# project4_v1.net
KiCad netlist of a schematic drawn in Altium Designer
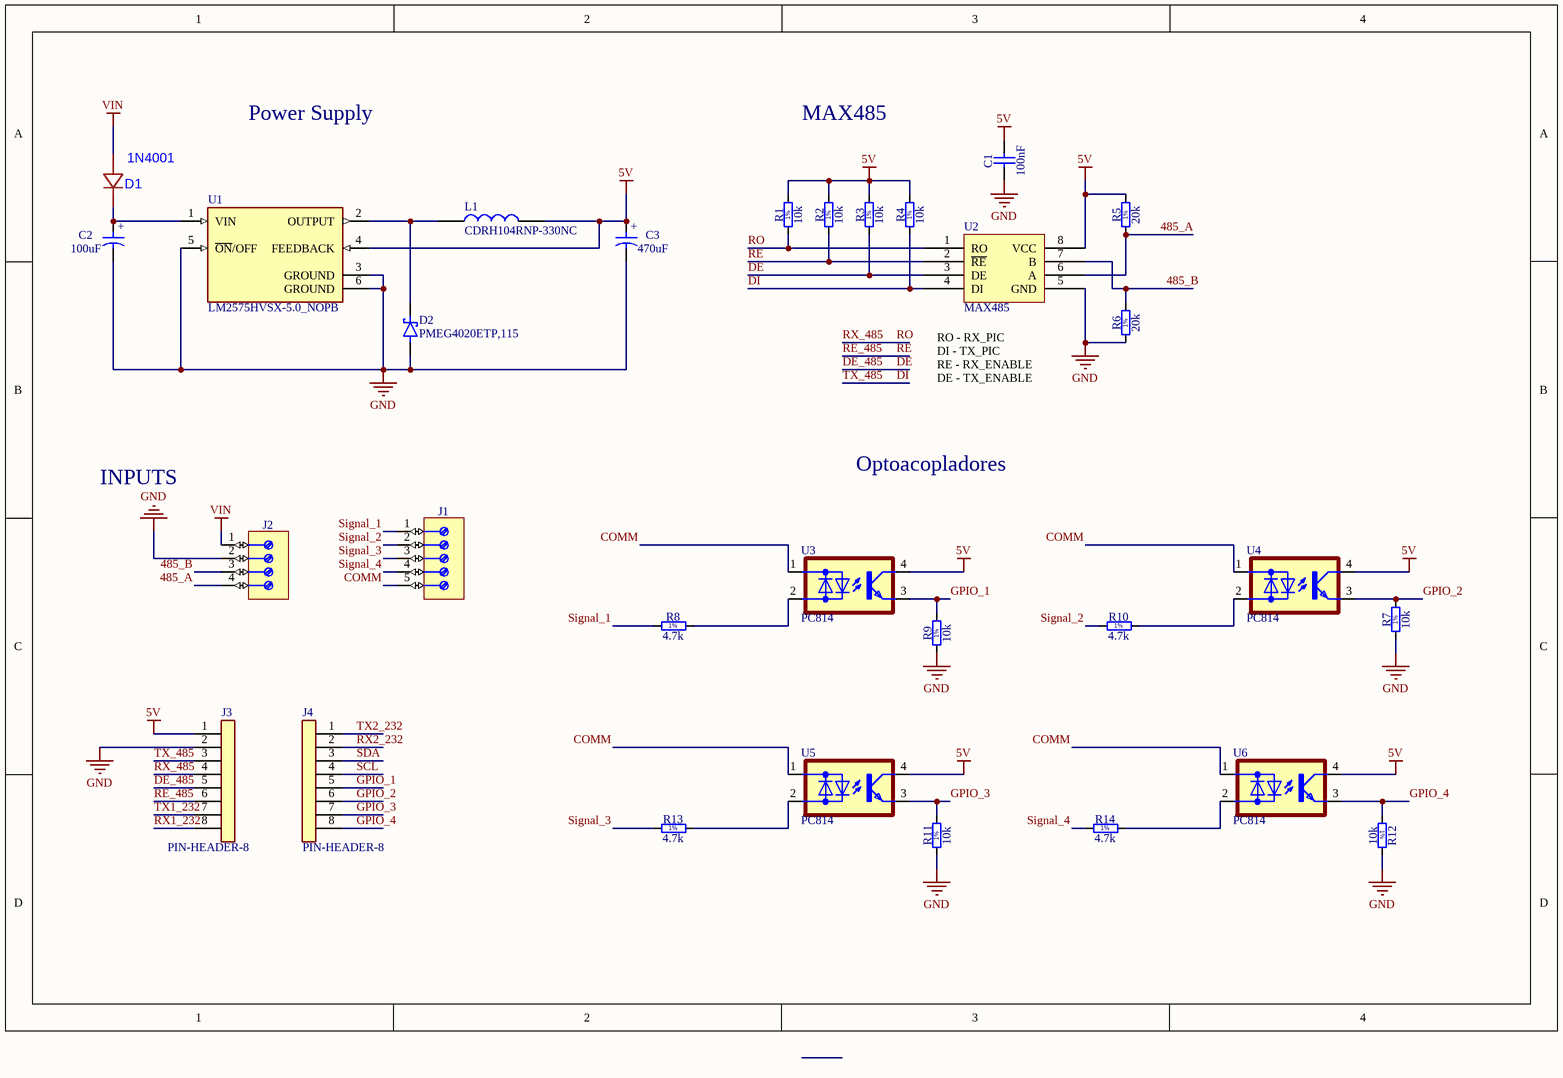
[diagram p0: project4_v1.SchDoc]

(export (version "E")
  (design (tool "Eeschema 10.0.6"))
  (components
    (comp (ref "C1")
      (value "100nF")
      (footprint "CAPC2012X135N")
      (description "Non-polarised capacitor")
      (fields
        (field (name "PART NUMBER") "CC0805_100NF_50V_10%_X7R")
        (field (name "VOLTAGE") "50V")
        (field (name "AUTHOR") "CERN DEM JLC")
      )
      (libsource (lib "Capacitors") (part "Capacitor - non polarized"))
    )
    (comp (ref "C2")
      (value "100uF")
      (footprint "CAPAE830X1020N")
      (description "Polarised capacitor")
      (fields
        (field (name "PART NUMBER") "CAE830-1020_100UF_35V_20%")
        (field (name "VOLTAGE") "35V")
        (field (name "AUTHOR") "CERN DEM JLC")
      )
      (libsource (lib "Capacitors") (part "Capacitor - polarized"))
    )
    (comp (ref "C3")
      (value "470uF")
      (footprint "CAPAE1030X1020N")
      (description "Polarised capacitor")
      (fields
        (field (name "PART NUMBER") "CAE1030-1020_470UF_25V_20%")
        (field (name "VOLTAGE") "25V")
        (field (name "AUTHOR") "CERN DEM JLC")
      )
      (libsource (lib "Capacitors") (part "Capacitor - polarized"))
    )
    (comp (ref "D1")
      (value "1N4001")
      (footprint "SMA_L4.5-W2.7-LS5.2-RD")
      (fields (field (name "MANUFACTURER") "JSMSEMI(杰盛微)") (field (name "MANUFACTURER PART") "1N4001 M1"))
      (libsource (lib "Galio-complete") (part "1N4001 M1"))
    )
    (comp (ref "D2")
      (value "PMEG4020ETP,115")
      (footprint "SODFL4725X110N")
      (description "Diode Schottky 40V 2A Surface Mount SOD-128/CFP5")
      (fields (field (name "MF") "Nexperia USA"))
      (libsource (lib "Galio-complete") (part "PMEG4020ETP,115"))
    )
    (comp (ref "J1")
      (value "TRT5")
      (footprint "TRT_5_3.81_PLUG")
      (description "TRT_5")
      (libsource (lib "Galio-connectors") (part "TRT_5"))
    )
    (comp (ref "J2")
      (value "TRT4")
      (footprint "TRT_4_3.81_PLUG")
      (description "TRT_4")
      (libsource (lib "Galio-connectors") (part "TRT_4"))
    )
    (comp (ref "J3")
      (value "PIN-HEADER-8")
      (footprint "PIN-HEADER-8-FEMALE")
      (fields (field (name "MP") "MTSW-108-07-G-S-208"))
      (libsource (lib "") (part "PIN-HEADER-8_1"))
    )
    (comp (ref "J4")
      (value "PIN-HEADER-8")
      (footprint "PIN-HEADER-8-FEMALE")
      (fields (field (name "MP") "MTSW-108-07-G-S-208"))
      (libsource (lib "Galio-connectors") (part "PIN-HEADER-8"))
    )
    (comp (ref "L1")
      (value "CDRH104RNP-330NC")
      (footprint "IND-SMD_L10.2-W10.0")
      (description "Power Inductors - SMD 33uH 2.2A,33 H Shielded Inductor 2.2 A 93mOhm Max Nonstandard")
      (fields (field (name "MOUSER PART NUMBER") "851-CDRH104RNP-330NC"))
      (libsource (lib "Galio-complete") (part "CDRH104RNP-330NC"))
    )
    (comp (ref "R1")
      (value "10k")
      (footprint "RESC2012X60N")
      (description "Resistor - 1%")
      (fields
        (field (name "PART NUMBER") "R0805_10K_1%_0.125W_100PPM")
        (field (name "POWER") "0.125W")
        (field (name "AUTHOR") "CERN DEM JLC")
      )
      (libsource (lib "Resistors") (part "Resistor - 1%"))
    )
    (comp (ref "R2")
      (value "10k")
      (footprint "RESC2012X60N")
      (description "Resistor - 1%")
      (fields
        (field (name "PART NUMBER") "R0805_10K_1%_0.125W_100PPM")
        (field (name "POWER") "0.125W")
        (field (name "AUTHOR") "CERN DEM JLC")
      )
      (libsource (lib "Resistors") (part "Resistor - 1%"))
    )
    (comp (ref "R3")
      (value "10k")
      (footprint "RESC2012X60N")
      (description "Resistor - 1%")
      (fields
        (field (name "PART NUMBER") "R0805_10K_1%_0.125W_100PPM")
        (field (name "POWER") "0.125W")
        (field (name "AUTHOR") "CERN DEM JLC")
      )
      (libsource (lib "Resistors") (part "Resistor - 1%"))
    )
    (comp (ref "R4")
      (value "10k")
      (footprint "RESC2012X60N")
      (description "Resistor - 1%")
      (fields
        (field (name "PART NUMBER") "R0805_10K_1%_0.125W_100PPM")
        (field (name "POWER") "0.125W")
        (field (name "AUTHOR") "CERN DEM JLC")
      )
      (libsource (lib "Resistors") (part "Resistor - 1%"))
    )
    (comp (ref "R5")
      (value "20k")
      (footprint "RESC2012X60N")
      (description "Resistor - 1%")
      (fields
        (field (name "PART NUMBER") "R0805_20K_1%_0.125W_100PPM")
        (field (name "POWER") "0.125W")
        (field (name "AUTHOR") "CERN DEM JLC")
      )
      (libsource (lib "Resistors") (part "Resistor - 1%"))
    )
    (comp (ref "R6")
      (value "20k")
      (footprint "RESC2012X60N")
      (description "Resistor - 1%")
      (fields
        (field (name "PART NUMBER") "R0805_20K_1%_0.125W_100PPM")
        (field (name "POWER") "0.125W")
        (field (name "AUTHOR") "CERN DEM JLC")
      )
      (libsource (lib "Resistors") (part "Resistor - 1%"))
    )
    (comp (ref "R7")
      (value "10k")
      (footprint "RESC2012X60N")
      (description "Resistor - 1%")
      (fields
        (field (name "PART NUMBER") "R0805_10K_1%_0.125W_100PPM")
        (field (name "POWER") "0.125W")
        (field (name "AUTHOR") "CERN DEM JLC")
      )
      (libsource (lib "Resistors") (part "Resistor - 1%"))
    )
    (comp (ref "R8")
      (value "4.7k")
      (footprint "RESC2012X60N")
      (description "Resistor - 1%")
      (fields
        (field (name "PART NUMBER") "R0805_10K_1%_0.125W_100PPM")
        (field (name "POWER") "0.125W")
        (field (name "AUTHOR") "CERN DEM JLC")
      )
      (libsource (lib "Resistors") (part "Resistor - 1%"))
    )
    (comp (ref "R9")
      (value "10k")
      (footprint "RESC2012X60N")
      (description "Resistor - 1%")
      (fields
        (field (name "PART NUMBER") "R0805_10K_1%_0.125W_100PPM")
        (field (name "POWER") "0.125W")
        (field (name "AUTHOR") "CERN DEM JLC")
      )
      (libsource (lib "Resistors") (part "Resistor - 1%"))
    )
    (comp (ref "R10")
      (value "4.7k")
      (footprint "RESC2012X60N")
      (description "Resistor - 1%")
      (fields
        (field (name "PART NUMBER") "R0805_10K_1%_0.125W_100PPM")
        (field (name "POWER") "0.125W")
        (field (name "AUTHOR") "CERN DEM JLC")
      )
      (libsource (lib "Resistors") (part "Resistor - 1%"))
    )
    (comp (ref "R11")
      (value "10k")
      (footprint "RESC2012X60N")
      (description "Resistor - 1%")
      (fields
        (field (name "PART NUMBER") "R0805_10K_1%_0.125W_100PPM")
        (field (name "POWER") "0.125W")
        (field (name "AUTHOR") "CERN DEM JLC")
      )
      (libsource (lib "Resistors") (part "Resistor - 1%"))
    )
    (comp (ref "R12")
      (value "10k")
      (footprint "RESC2012X60N")
      (description "Resistor - 1%")
      (fields
        (field (name "PART NUMBER") "R0805_10K_1%_0.125W_100PPM")
        (field (name "POWER") "0.125W")
        (field (name "AUTHOR") "CERN DEM JLC")
      )
      (libsource (lib "Resistors") (part "Resistor - 1%"))
    )
    (comp (ref "R13")
      (value "4.7k")
      (footprint "RESC2012X60N")
      (description "Resistor - 1%")
      (fields
        (field (name "PART NUMBER") "R0805_10K_1%_0.125W_100PPM")
        (field (name "POWER") "0.125W")
        (field (name "AUTHOR") "CERN DEM JLC")
      )
      (libsource (lib "Resistors") (part "Resistor - 1%"))
    )
    (comp (ref "R14")
      (value "4.7k")
      (footprint "RESC2012X60N")
      (description "Resistor - 1%")
      (fields
        (field (name "PART NUMBER") "R0805_10K_1%_0.125W_100PPM")
        (field (name "POWER") "0.125W")
        (field (name "AUTHOR") "CERN DEM JLC")
      )
      (libsource (lib "Resistors") (part "Resistor - 1%"))
    )
    (comp (ref "U1")
      (value "LM2575HVSX-5.0_NOPB")
      (footprint "TO-263-5_L10.0-W8.4-P1.70-LS15.3-BR")
      (fields (field (name "MF") "UMW") (field (name "MP") "LM2575S-5.0"))
      (libsource (lib "Galio-complete") (part "LM2575HVSX-5.0_NOPB"))
    )
    (comp (ref "U2")
      (value "MAX485")
      (footprint "SOIC8-N_MC")
      (libsource (lib "Galio-complete") (part "MAX485"))
    )
    (comp (ref "U3")
      (value "PC814")
      (footprint "PC814BS")
      (description "Optoacoplador com saÃ­da de transistor de 5000Vrms, 1 canal, 4 componentes SMD.")
      (fields (field (name "MF") "Essentra Components"))
      (libsource (lib "Galio-complete") (part "PC814"))
    )
    (comp (ref "U4")
      (value "PC814")
      (footprint "PC814BS")
      (description "Optoacoplador com saÃ­da de transistor de 5000Vrms, 1 canal, 4 componentes SMD.")
      (fields (field (name "MF") "Essentra Components"))
      (libsource (lib "Galio-complete") (part "PC814"))
    )
    (comp (ref "U5")
      (value "PC814")
      (footprint "PC814BS")
      (description "Optoacoplador com saÃ­da de transistor de 5000Vrms, 1 canal, 4 componentes SMD.")
      (fields (field (name "MF") "Essentra Components"))
      (libsource (lib "Galio-complete") (part "PC814"))
    )
    (comp (ref "U6")
      (value "PC814")
      (footprint "PC814BS")
      (description "Optoacoplador com saÃ­da de transistor de 5000Vrms, 1 canal, 4 componentes SMD.")
      (fields (field (name "MF") "Essentra Components"))
      (libsource (lib "Galio-complete") (part "PC814"))
    )
  )
  (nets
    (net (code "1") (name "/485_A") (class "Default")
      (node (ref "J2") (pin "4") (pinfunction "4_4") (pintype "bidirectional"))
      (node (ref "R5") (pin "1") (pinfunction "1_1") (pintype "passive"))
      (node (ref "U2") (pin "6") (pinfunction "A_6") (pintype "passive"))
    )
    (net (code "2") (name "/485_B") (class "Default")
      (node (ref "J2") (pin "3") (pinfunction "3_3") (pintype "bidirectional"))
      (node (ref "R6") (pin "2") (pinfunction "2_2") (pintype "passive"))
      (node (ref "U2") (pin "7") (pinfunction "B_7") (pintype "passive"))
    )
    (net (code "3") (name "/COMM") (class "Default")
      (node (ref "J1") (pin "5") (pinfunction "5_5") (pintype "bidirectional"))
      (node (ref "U3") (pin "1") (pinfunction "AC1_1") (pintype "passive"))
      (node (ref "U4") (pin "1") (pinfunction "AC1_1") (pintype "passive"))
      (node (ref "U5") (pin "1") (pinfunction "AC1_1") (pintype "passive"))
      (node (ref "U6") (pin "1") (pinfunction "AC1_1") (pintype "passive"))
    )
    (net (code "4") (name "/DE") (class "Default")
      (node (ref "J3") (pin "5") (pintype "passive"))
      (node (ref "R3") (pin "1") (pinfunction "1_1") (pintype "passive"))
      (node (ref "U2") (pin "3") (pinfunction "DE_3") (pintype "passive"))
    )
    (net (code "5") (name "/DI") (class "Default")
      (node (ref "J3") (pin "3") (pintype "passive"))
      (node (ref "R4") (pin "1") (pinfunction "1_1") (pintype "passive"))
      (node (ref "U2") (pin "4") (pinfunction "DI_4") (pintype "passive"))
    )
    (net (code "6") (name "/GPIO_1") (class "Default")
      (node (ref "J4") (pin "5") (pintype "passive"))
      (node (ref "R9") (pin "2") (pinfunction "2_2") (pintype "passive"))
      (node (ref "U3") (pin "3") (pinfunction "E_3") (pintype "passive"))
    )
    (net (code "7") (name "/GPIO_2") (class "Default")
      (node (ref "J4") (pin "6") (pintype "passive"))
      (node (ref "R7") (pin "2") (pinfunction "2_2") (pintype "passive"))
      (node (ref "U4") (pin "3") (pinfunction "E_3") (pintype "passive"))
    )
    (net (code "8") (name "/GPIO_3") (class "Default")
      (node (ref "J4") (pin "7") (pintype "passive"))
      (node (ref "R11") (pin "2") (pinfunction "2_2") (pintype "passive"))
      (node (ref "U5") (pin "3") (pinfunction "E_3") (pintype "passive"))
    )
    (net (code "9") (name "/GPIO_4") (class "Default")
      (node (ref "J4") (pin "8") (pintype "passive"))
      (node (ref "R12") (pin "1") (pinfunction "1_1") (pintype "passive"))
      (node (ref "U6") (pin "3") (pinfunction "E_3") (pintype "passive"))
    )
    (net (code "10") (name "/RE") (class "Default")
      (node (ref "J3") (pin "6") (pintype "passive"))
      (node (ref "R2") (pin "1") (pinfunction "1_1") (pintype "passive"))
      (node (ref "U2") (pin "2") (pinfunction "~{RE}_2") (pintype "passive"))
    )
    (net (code "11") (name "/RO") (class "Default")
      (node (ref "J3") (pin "4") (pintype "passive"))
      (node (ref "R1") (pin "1") (pinfunction "1_1") (pintype "passive"))
      (node (ref "U2") (pin "1") (pinfunction "RO_1") (pintype "passive"))
    )
    (net (code "12") (name "/RX1_232") (class "Default") (node (ref "J3") (pin "8") (pintype "passive")))
    (net (code "13") (name "/RX2_232") (class "Default") (node (ref "J4") (pin "2") (pintype "passive")))
    (net (code "14") (name "/SCL") (class "Default") (node (ref "J4") (pin "4") (pintype "passive")))
    (net (code "15") (name "/SDA") (class "Default") (node (ref "J4") (pin "3") (pintype "passive")))
    (net (code "16") (name "/Signal_1") (class "Default")
      (node (ref "J1") (pin "1") (pinfunction "1_1") (pintype "bidirectional"))
      (node (ref "R8") (pin "1") (pinfunction "1_1") (pintype "passive"))
    )
    (net (code "17") (name "/Signal_2") (class "Default")
      (node (ref "J1") (pin "2") (pinfunction "2_2") (pintype "bidirectional"))
      (node (ref "R10") (pin "1") (pinfunction "1_1") (pintype "passive"))
    )
    (net (code "18") (name "/Signal_3") (class "Default")
      (node (ref "J1") (pin "3") (pinfunction "3_3") (pintype "bidirectional"))
      (node (ref "R13") (pin "1") (pinfunction "1_1") (pintype "passive"))
    )
    (net (code "19") (name "/Signal_4") (class "Default")
      (node (ref "J1") (pin "4") (pinfunction "4_4") (pintype "bidirectional"))
      (node (ref "R14") (pin "1") (pinfunction "1_1") (pintype "passive"))
    )
    (net (code "20") (name "/TX1_232") (class "Default") (node (ref "J3") (pin "7") (pintype "passive")))
    (net (code "21") (name "/TX2_232") (class "Default") (node (ref "J4") (pin "1") (pintype "passive")))
    (net (code "22") (name "5V") (class "Default")
      (node (ref "C1") (pin "2") (pinfunction "2_2") (pintype "passive"))
      (node (ref "C3") (pin "1") (pinfunction "1_1") (pintype "passive"))
      (node (ref "J3") (pin "1") (pintype "passive"))
      (node (ref "L1") (pin "2") (pinfunction "2_2") (pintype "passive"))
      (node (ref "R1") (pin "2") (pinfunction "2_2") (pintype "passive"))
      (node (ref "R2") (pin "2") (pinfunction "2_2") (pintype "passive"))
      (node (ref "R3") (pin "2") (pinfunction "2_2") (pintype "passive"))
      (node (ref "R4") (pin "2") (pinfunction "2_2") (pintype "passive"))
      (node (ref "R5") (pin "2") (pinfunction "2_2") (pintype "passive"))
      (node (ref "U1") (pin "4") (pinfunction "FEEDBACK_4") (pintype "input"))
      (node (ref "U2") (pin "8") (pinfunction "VCC_8") (pintype "power_in"))
      (node (ref "U3") (pin "4") (pinfunction "C_4") (pintype "passive"))
      (node (ref "U4") (pin "4") (pinfunction "C_4") (pintype "passive"))
      (node (ref "U5") (pin "4") (pinfunction "C_4") (pintype "passive"))
      (node (ref "U6") (pin "4") (pinfunction "C_4") (pintype "passive"))
    )
    (net (code "23") (name "GND") (class "Default")
      (node (ref "C1") (pin "1") (pinfunction "1_1") (pintype "passive"))
      (node (ref "C2") (pin "2") (pinfunction "2_2") (pintype "passive"))
      (node (ref "C3") (pin "2") (pinfunction "2_2") (pintype "passive"))
      (node (ref "D2") (pin "2") (pinfunction "A_2") (pintype "passive"))
      (node (ref "J2") (pin "2") (pinfunction "2_2") (pintype "bidirectional"))
      (node (ref "J3") (pin "2") (pintype "passive"))
      (node (ref "R11") (pin "1") (pinfunction "1_1") (pintype "passive"))
      (node (ref "R12") (pin "2") (pinfunction "2_2") (pintype "passive"))
      (node (ref "R6") (pin "1") (pinfunction "1_1") (pintype "passive"))
      (node (ref "R7") (pin "1") (pinfunction "1_1") (pintype "passive"))
      (node (ref "R9") (pin "1") (pinfunction "1_1") (pintype "passive"))
      (node (ref "U1") (pin "3") (pinfunction "GROUND_3") (pintype "power_in"))
      (node (ref "U1") (pin "5") (pinfunction "~{ON}/OFF_5") (pintype "input"))
      (node (ref "U1") (pin "6") (pinfunction "GROUND_6") (pintype "power_in"))
      (node (ref "U2") (pin "5") (pinfunction "GND_5") (pintype "power_in"))
    )
    (net (code "24") (name "Net-(D1-K)") (class "Default")
      (node (ref "C2") (pin "1") (pinfunction "1_1") (pintype "passive"))
      (node (ref "D1") (pin "1") (pinfunction "K_1") (pintype "passive"))
      (node (ref "U1") (pin "1") (pinfunction "VIN_1") (pintype "input"))
    )
    (net (code "25") (name "Net-(D2-K)") (class "Default")
      (node (ref "D2") (pin "1") (pinfunction "K_1") (pintype "passive"))
      (node (ref "L1") (pin "1") (pinfunction "1_1") (pintype "passive"))
      (node (ref "U1") (pin "2") (pinfunction "OUTPUT_2") (pintype "output"))
    )
    (net (code "26") (name "Net-(U3-AC2)") (class "Default")
      (node (ref "R8") (pin "2") (pinfunction "2_2") (pintype "passive"))
      (node (ref "U3") (pin "2") (pinfunction "AC2_2") (pintype "passive"))
    )
    (net (code "27") (name "Net-(U4-AC2)") (class "Default")
      (node (ref "R10") (pin "2") (pinfunction "2_2") (pintype "passive"))
      (node (ref "U4") (pin "2") (pinfunction "AC2_2") (pintype "passive"))
    )
    (net (code "28") (name "Net-(U5-AC2)") (class "Default")
      (node (ref "R13") (pin "2") (pinfunction "2_2") (pintype "passive"))
      (node (ref "U5") (pin "2") (pinfunction "AC2_2") (pintype "passive"))
    )
    (net (code "29") (name "Net-(U6-AC2)") (class "Default")
      (node (ref "R14") (pin "2") (pinfunction "2_2") (pintype "passive"))
      (node (ref "U6") (pin "2") (pinfunction "AC2_2") (pintype "passive"))
    )
    (net (code "30") (name "VIN") (class "Default")
      (node (ref "D1") (pin "2") (pinfunction "A_2") (pintype "passive"))
      (node (ref "J2") (pin "1") (pinfunction "1_1") (pintype "bidirectional"))
    )
  )
)
